# SCHEMATICS.net
KiCad netlist of a schematic drawn in EAGLE
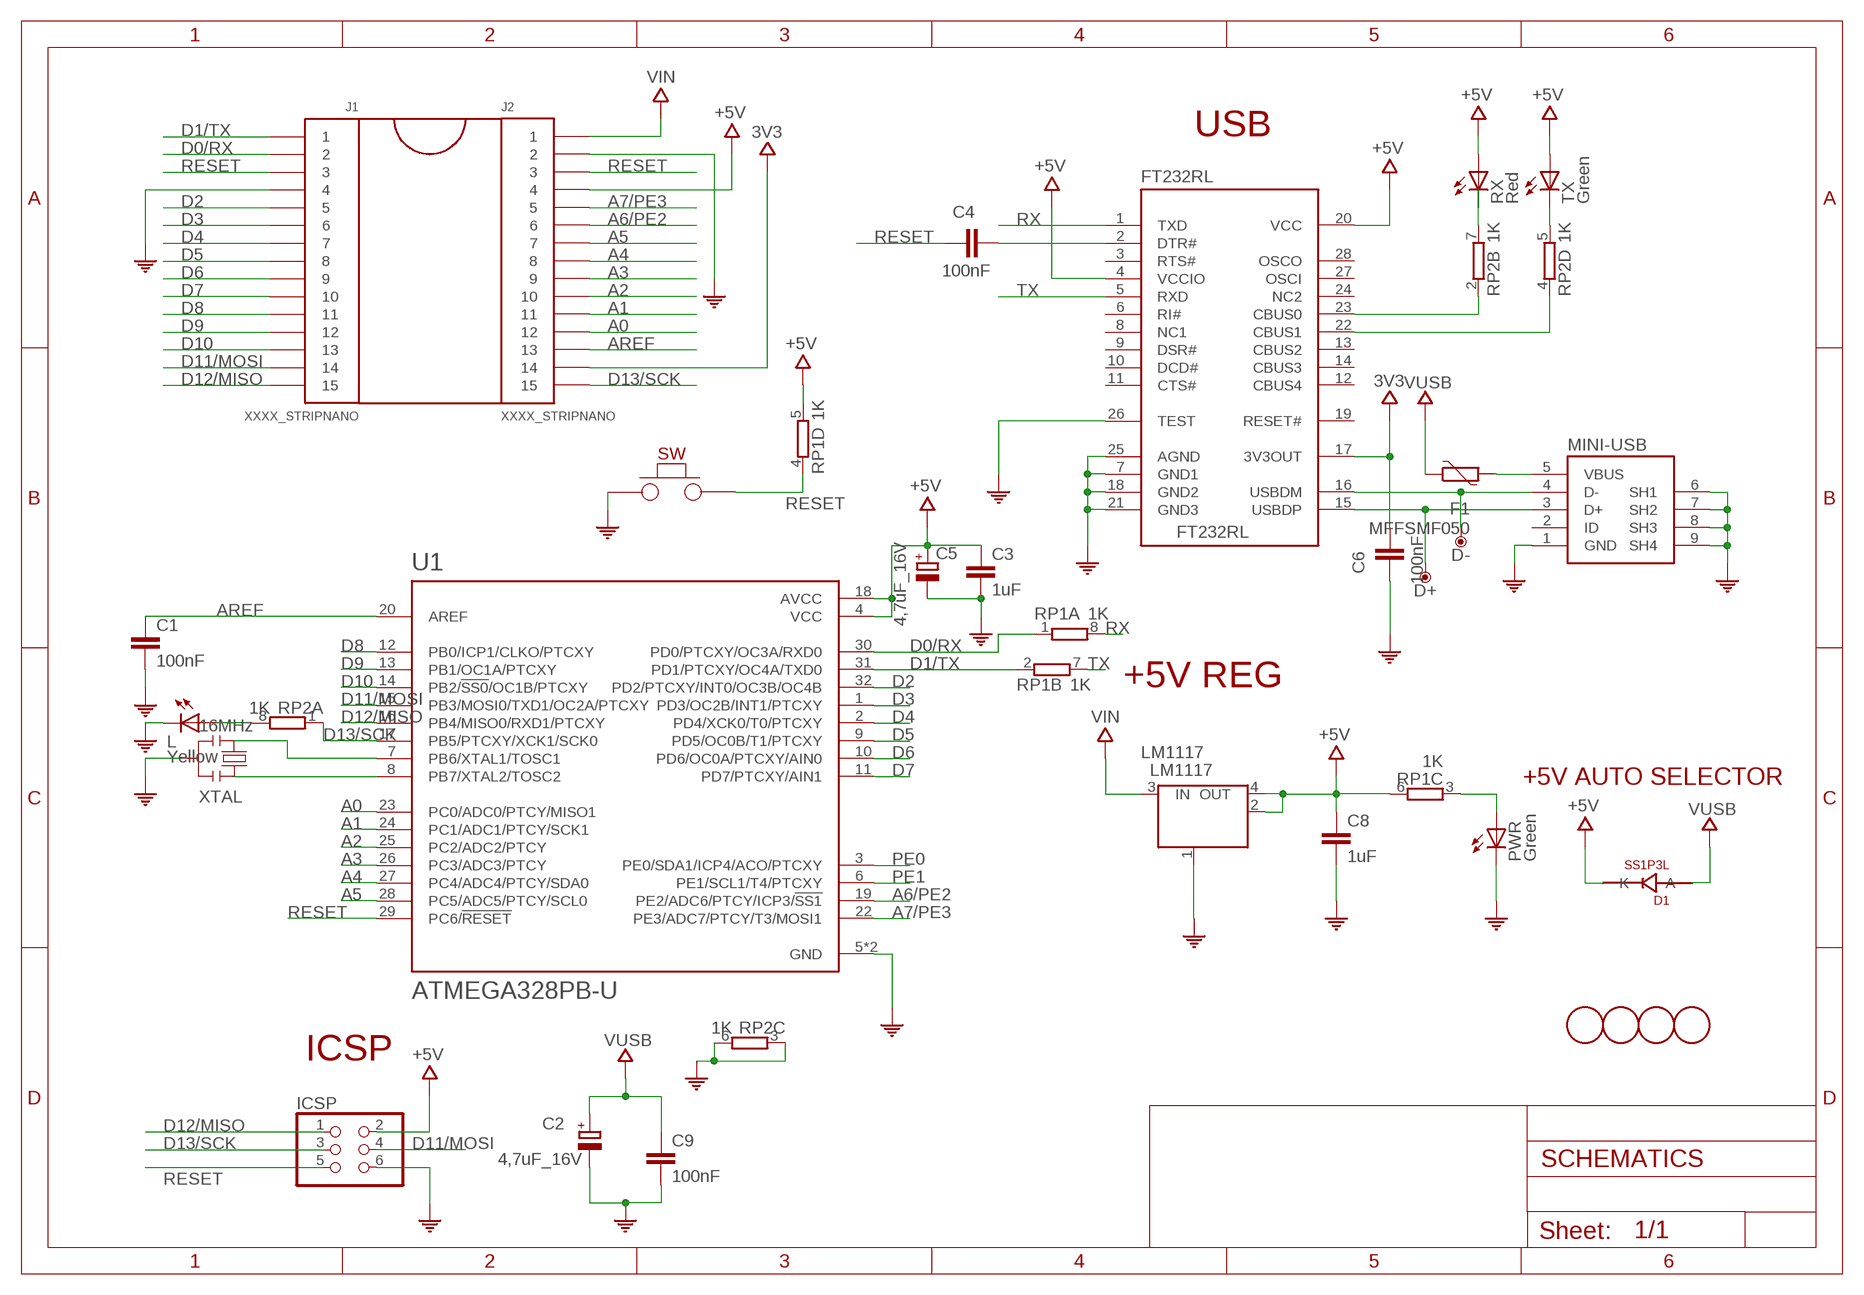
[diagram p0: schematic, sheet 1]

(export (version "E")
  (design (tool "Eeschema 10.0.6"))
  (components
    (comp (ref "C1")
      (value "100nF")
      (footprint "eagle-import:C0603-ROUND")
      (fields (field (name "PART_NUMBER") "cl10b104kbnc"))
      (libsource (lib "eagle-import") (part "0015_100NF_0603"))
    )
    (comp (ref "C2")
      (value "4,7uF_16V")
      (footprint "eagle-import:TAN-A")
      (fields (field (name "PART_NUMBER") "TAJA475MO16RNJ"))
      (libsource (lib "eagle-import") (part "0833_TAJA475MO16RNJ"))
    )
    (comp (ref "C3")
      (value "1uF")
      (footprint "eagle-import:C0603-ROUND")
      (fields (field (name "PART_NUMBER") "1uF_0603/GRM188R61E105KA12D"))
      (libsource (lib "eagle-import") (part "0006_1UF_0603/GRM188R61E105KA12D"))
    )
    (comp (ref "C4")
      (value "100nF")
      (footprint "eagle-import:C0603-ROUND")
      (fields (field (name "PART_NUMBER") "cl10b104kbnc"))
      (libsource (lib "eagle-import") (part "0015_100NF_0603"))
    )
    (comp (ref "C5")
      (value "4,7uF_16V")
      (footprint "eagle-import:TAN-A")
      (fields (field (name "PART_NUMBER") "TAJA475MO16RNJ"))
      (libsource (lib "eagle-import") (part "0833_TAJA475MO16RNJ"))
    )
    (comp (ref "C6")
      (value "100nF")
      (footprint "eagle-import:C0603-ROUND")
      (fields (field (name "PART_NUMBER") "cl10b104kbnc"))
      (libsource (lib "eagle-import") (part "0015_100NF_0603"))
    )
    (comp (ref "C8")
      (value "1uF")
      (footprint "eagle-import:C0603-ROUND")
      (fields (field (name "PART_NUMBER") "1uF_0603/GRM188R61E105KA12D"))
      (libsource (lib "eagle-import") (part "0006_1UF_0603/GRM188R61E105KA12D"))
    )
    (comp (ref "C9")
      (value "100nF")
      (footprint "eagle-import:C0603-ROUND")
      (fields (field (name "PART_NUMBER") "cl10b104kbnc"))
      (libsource (lib "eagle-import") (part "0015_100NF_0603"))
    )
    (comp (ref "D+")
      (value "DNP")
      (footprint "eagle-import:TP-1.00MM")
      (libsource (lib "eagle-import") (part "TPTP-1.00MM"))
    )
    (comp (ref "D-")
      (value "DNP")
      (footprint "eagle-import:TP-1.00MM")
      (libsource (lib "eagle-import") (part "TPTP-1.00MM"))
    )
    (comp (ref "D1")
      (value "SS1P3L")
      (footprint "eagle-import:DO220AAL")
      (fields (field (name "PART_NUMBER") "SS1P3L-M3/84A"))
      (libsource (lib "eagle-import") (part "0025_SS1P3L-M3/84A"))
    )
    (comp (ref "F1")
      (value "MFFSMF050")
      (footprint "eagle-import:0603-1608X90N")
      (fields (field (name "MANUFACTURER") "Bourns Inc "))
      (libsource (lib "eagle-import") (part "PTC"))
    )
    (comp (ref "FT232RL")
      (value "FT232RL")
      (footprint "eagle-import:SSOP28")
      (libsource (lib "eagle-import") (part "0226_FT232RL"))
    )
    (comp (ref "ICSP")
      (value "0114_PH254-203DF118A00V")
      (footprint "eagle-import:2X03")
      (fields (field (name "PART_NUMBER") "PH254-203DF118A00V"))
      (libsource (lib "eagle-import") (part "0114_PH254-203DF118A00V"))
    )
    (comp (ref "J1")
      (value "XXXX_STRIPNANO")
      (footprint "eagle-import:HEAD15-NOSS")
      (libsource (lib "eagle-import") (part "XXXX_STRIPNANO"))
    )
    (comp (ref "J2")
      (value "XXXX_STRIPNANO")
      (footprint "eagle-import:HEAD15-NOSS")
      (libsource (lib "eagle-import") (part "XXXX_STRIPNANO"))
    )
    (comp (ref "L")
      (value "Yellow")
      (footprint "eagle-import:CHIPLED_0805")
      (fields (field (name "PART_NUMBER") "KPT-2012YC"))
      (libsource (lib "eagle-import") (part "0044_KPT-2012YC"))
    )
    (comp (ref "LM1117")
      (value "LM1117")
      (footprint "eagle-import:LINEAR_SOT223")
      (fields (field (name "PART_NUMBER") "LM1117IMPX-5.0"))
      (libsource (lib "eagle-import") (part "0022_LM1117IMPX-5.0"))
    )
    (comp (ref "MINI-USB")
      (value "0219_14850")
      (footprint "eagle-import:USB-MINI-B_2")
      (fields (field (name "PART_NUMBER") "14850"))
      (libsource (lib "eagle-import") (part "0219_14850"))
    )
    (comp (ref "P0INT_2")
      (value "DNP")
      (footprint "eagle-import:FD-1-1.5")
      (libsource (lib "eagle-import") (part "FIDUCIAL-1.5MM"))
    )
    (comp (ref "POINT_1")
      (value "DNP")
      (footprint "eagle-import:FD-1-1.5")
      (libsource (lib "eagle-import") (part "FIDUCIAL-1.5MM"))
    )
    (comp (ref "POINT_A")
      (value "DNP")
      (footprint "eagle-import:FD-1-1.5")
      (libsource (lib "eagle-import") (part "FIDUCIAL-1.5MM"))
    )
    (comp (ref "POINT_B")
      (value "DNP")
      (footprint "eagle-import:FD-1-1.5")
      (libsource (lib "eagle-import") (part "FIDUCIAL-1.5MM"))
    )
    (comp (ref "PWR")
      (value "Green")
      (footprint "eagle-import:CHIPLED_0805")
      (fields (field (name "PART_NUMBER") "KPT-2012SGC"))
      (libsource (lib "eagle-import") (part "0043_KPT-2012SGC"))
    )
    (comp (ref "RP1")
      (value "1K")
      (footprint "eagle-import:CAY16")
      (fields (field (name "PART_NUMBER") "064R_1K_/_CAY16-102J4LF"))
      (libsource (lib "eagle-import") (part "0005_064R_1K_/_CAY16-102J4LF"))
    )
    (comp (ref "RP2")
      (value "1K")
      (footprint "eagle-import:CAY16")
      (fields (field (name "PART_NUMBER") "064R_1K_/_CAY16-102J4LF"))
      (libsource (lib "eagle-import") (part "0005_064R_1K_/_CAY16-102J4LF"))
    )
    (comp (ref "RX")
      (value "Red")
      (footprint "eagle-import:CHIPLED_0805")
      (fields (field (name "PART_NUMBER") "KTP-2012SURCK"))
      (libsource (lib "eagle-import") (part "0181_KTP-2012SURCK"))
    )
    (comp (ref "TX")
      (value "Green")
      (footprint "eagle-import:CHIPLED_0805")
      (fields (field (name "PART_NUMBER") "KPT-2012SGC"))
      (libsource (lib "eagle-import") (part "0043_KPT-2012SGC"))
    )
    (comp (ref "U$4")
      (value "3*6*4.2H260g")
      (footprint "eagle-import:3_6_4.3_PUSH_SWITCH")
      (libsource (lib "eagle-import") (part "364.3_PUSH_SWITCH"))
    )
    (comp (ref "U1")
      (value "ATMEGA328PB-U")
      (footprint "eagle-import:QFP80P900X900X120-32N")
      (fields (field (name "MF") "Microchip Technology"))
      (libsource (lib "eagle-import") (part "ATMEGA328PB-AN"))
    )
    (comp (ref "XTAL")
      (value "16MHz")
      (footprint "eagle-import:RESONATOR")
      (fields (field (name "PART_NUMBER") "CSTCE16M0V53-R0"))
      (libsource (lib "eagle-import") (part "0011_CSTCE16M0V53-R0"))
    )
  )
  (nets
    (net (code "1") (name "+5V") (class "Default")
      (node (ref "C3") (pin "1") (pinfunction "1_1") (pintype "passive"))
      (node (ref "C5") (pin "1") (pinfunction "+_1") (pintype "passive"))
      (node (ref "C8") (pin "1") (pinfunction "1_1") (pintype "passive"))
      (node (ref "D1") (pin "P$1") (pinfunction "K_P$1") (pintype "bidirectional"))
      (node (ref "FT232RL") (pin "20") (pinfunction "VCC_20") (pintype "power_in"))
      (node (ref "FT232RL") (pin "4") (pinfunction "VCCIO_4") (pintype "power_in"))
      (node (ref "ICSP") (pin "2") (pinfunction "2_2") (pintype "passive"))
      (node (ref "J2") (pin "4") (pinfunction "4_4") (pintype "passive"))
      (node (ref "LM1117") (pin "2") (pinfunction "OUT_2") (pintype "passive"))
      (node (ref "LM1117") (pin "4") (pinfunction "OUT_4") (pintype "passive"))
      (node (ref "RP1") (pin "5") (pinfunction "2_5") (pintype "passive"))
      (node (ref "RP1") (pin "6") (pinfunction "2_6") (pintype "passive"))
      (node (ref "RX") (pin "A") (pinfunction "A_A") (pintype "passive"))
      (node (ref "TX") (pin "A") (pinfunction "A_A") (pintype "passive"))
      (node (ref "U1") (pin "18") (pinfunction "AVCC_18") (pintype "power_in"))
      (node (ref "U1") (pin "4") (pinfunction "VCC_4") (pintype "power_in"))
    )
    (net (code "2") (name "/A0") (class "Default")
      (node (ref "J2") (pin "12") (pinfunction "12_12") (pintype "passive"))
      (node (ref "U1") (pin "23") (pinfunction "PC0/ADC0/PTCY/MISO1_23") (pintype "bidirectional"))
    )
    (net (code "3") (name "/A1") (class "Default")
      (node (ref "J2") (pin "11") (pinfunction "11_11") (pintype "passive"))
      (node (ref "U1") (pin "24") (pinfunction "PC1/ADC1/PTCY/SCK1_24") (pintype "bidirectional"))
    )
    (net (code "4") (name "/A2") (class "Default")
      (node (ref "J2") (pin "10") (pinfunction "10_10") (pintype "passive"))
      (node (ref "U1") (pin "25") (pinfunction "PC2/ADC2/PTCY_25") (pintype "bidirectional"))
    )
    (net (code "5") (name "/A3") (class "Default")
      (node (ref "J2") (pin "9") (pinfunction "9_9") (pintype "passive"))
      (node (ref "U1") (pin "26") (pinfunction "PC3/ADC3/PTCY_26") (pintype "bidirectional"))
    )
    (net (code "6") (name "/A4") (class "Default")
      (node (ref "J2") (pin "8") (pinfunction "8_8") (pintype "passive"))
      (node (ref "U1") (pin "27") (pinfunction "PC4/ADC4/PTCY/SDA0_27") (pintype "bidirectional"))
    )
    (net (code "7") (name "/A5") (class "Default")
      (node (ref "J2") (pin "7") (pinfunction "7_7") (pintype "passive"))
      (node (ref "U1") (pin "28") (pinfunction "PC5/ADC5/PTCY/SCL0_28") (pintype "bidirectional"))
    )
    (net (code "8") (name "/A6{slash}PE2") (class "Default")
      (node (ref "J2") (pin "6") (pinfunction "6_6") (pintype "passive"))
      (node (ref "U1") (pin "19") (pinfunction "PE2/ADC6/PTCY/ICP3/~{SS1}_19") (pintype "bidirectional"))
    )
    (net (code "9") (name "/A7{slash}PE3") (class "Default")
      (node (ref "J2") (pin "5") (pinfunction "5_5") (pintype "passive"))
      (node (ref "U1") (pin "22") (pinfunction "PE3/ADC7/PTCY/T3/MOSI1_22") (pintype "bidirectional"))
    )
    (net (code "10") (name "/AREF") (class "Default")
      (node (ref "C1") (pin "1") (pinfunction "1_1") (pintype "passive"))
      (node (ref "J2") (pin "13") (pinfunction "13_13") (pintype "passive"))
      (node (ref "U1") (pin "20") (pinfunction "AREF_20") (pintype "input"))
    )
    (net (code "11") (name "/D0{slash}RX") (class "Default")
      (node (ref "J1") (pin "2") (pinfunction "2_2") (pintype "passive"))
      (node (ref "RP1") (pin "1") (pinfunction "1_1") (pintype "passive"))
      (node (ref "U1") (pin "30") (pinfunction "PD0/PTCXY/OC3A/RXD0_30") (pintype "bidirectional"))
    )
    (net (code "12") (name "/D1{slash}TX") (class "Default")
      (node (ref "J1") (pin "1") (pinfunction "1_1") (pintype "passive"))
      (node (ref "RP1") (pin "2") (pinfunction "1_2") (pintype "passive"))
      (node (ref "U1") (pin "31") (pinfunction "PD1/PTCXY/OC4A/TXD0_31") (pintype "bidirectional"))
    )
    (net (code "13") (name "/D2") (class "Default")
      (node (ref "J1") (pin "5") (pinfunction "5_5") (pintype "passive"))
      (node (ref "U1") (pin "32") (pinfunction "PD2/PTCXY/INT0/OC3B/OC4B_32") (pintype "bidirectional"))
    )
    (net (code "14") (name "/D3") (class "Default")
      (node (ref "J1") (pin "6") (pinfunction "6_6") (pintype "passive"))
      (node (ref "U1") (pin "1") (pinfunction "PD3/OC2B/INT1/PTCXY_1") (pintype "bidirectional"))
    )
    (net (code "15") (name "/D4") (class "Default")
      (node (ref "J1") (pin "7") (pinfunction "7_7") (pintype "passive"))
      (node (ref "U1") (pin "2") (pinfunction "PD4/XCK0/T0/PTCXY_2") (pintype "bidirectional"))
    )
    (net (code "16") (name "/D5") (class "Default")
      (node (ref "J1") (pin "8") (pinfunction "8_8") (pintype "passive"))
      (node (ref "U1") (pin "9") (pinfunction "PD5/OC0B/T1/PTCXY_9") (pintype "bidirectional"))
    )
    (net (code "17") (name "/D6") (class "Default")
      (node (ref "J1") (pin "9") (pinfunction "9_9") (pintype "passive"))
      (node (ref "U1") (pin "10") (pinfunction "PD6/OC0A/PTCXY/AIN0_10") (pintype "bidirectional"))
    )
    (net (code "18") (name "/D7") (class "Default")
      (node (ref "J1") (pin "10") (pinfunction "10_10") (pintype "passive"))
      (node (ref "U1") (pin "11") (pinfunction "PD7/PTCXY/AIN1_11") (pintype "bidirectional"))
    )
    (net (code "19") (name "/D8") (class "Default")
      (node (ref "J1") (pin "11") (pinfunction "11_11") (pintype "passive"))
      (node (ref "U1") (pin "12") (pinfunction "PB0/ICP1/CLKO/PTCXY_12") (pintype "bidirectional"))
    )
    (net (code "20") (name "/D9") (class "Default")
      (node (ref "J1") (pin "12") (pinfunction "12_12") (pintype "passive"))
      (node (ref "U1") (pin "13") (pinfunction "PB1/OC1A/PTCXY_13") (pintype "bidirectional"))
    )
    (net (code "21") (name "/D10") (class "Default")
      (node (ref "J1") (pin "13") (pinfunction "13_13") (pintype "passive"))
      (node (ref "U1") (pin "14") (pinfunction "PB2/~{SS0}/OC1B/PTCXY_14") (pintype "bidirectional"))
    )
    (net (code "22") (name "/D11{slash}MOSI") (class "Default")
      (node (ref "ICSP") (pin "4") (pinfunction "4_4") (pintype "passive"))
      (node (ref "J1") (pin "14") (pinfunction "14_14") (pintype "passive"))
      (node (ref "U1") (pin "15") (pinfunction "PB3/MOSI0/TXD1/OC2A/PTCXY_15") (pintype "bidirectional"))
    )
    (net (code "23") (name "/D12{slash}MISO") (class "Default")
      (node (ref "ICSP") (pin "1") (pinfunction "1_1") (pintype "passive"))
      (node (ref "J1") (pin "15") (pinfunction "15_15") (pintype "passive"))
      (node (ref "U1") (pin "16") (pinfunction "PB4/MISO0/RXD1/PTCXY_16") (pintype "bidirectional"))
    )
    (net (code "24") (name "/D13{slash}SCK") (class "Default")
      (node (ref "ICSP") (pin "3") (pinfunction "3_3") (pintype "passive"))
      (node (ref "J2") (pin "15") (pinfunction "15_15") (pintype "passive"))
      (node (ref "RP2") (pin "1") (pinfunction "1_1") (pintype "passive"))
      (node (ref "U1") (pin "17") (pinfunction "PB5/PTCXY/XCK1/SCK0_17") (pintype "bidirectional"))
    )
    (net (code "25") (name "/PE0") (class "Default")
      (node (ref "U1") (pin "3") (pinfunction "PE0/SDA1/ICP4/ACO/PTCXY_3") (pintype "bidirectional"))
    )
    (net (code "26") (name "/PE1") (class "Default")
      (node (ref "U1") (pin "6") (pinfunction "PE1/SCL1/T4/PTCXY_6") (pintype "bidirectional"))
    )
    (net (code "27") (name "/RESET") (class "Default")
      (node (ref "C4") (pin "1") (pinfunction "1_1") (pintype "passive"))
      (node (ref "ICSP") (pin "5") (pinfunction "5_5") (pintype "passive"))
      (node (ref "J1") (pin "3") (pinfunction "3_3") (pintype "passive"))
      (node (ref "J2") (pin "3") (pinfunction "3_3") (pintype "passive"))
      (node (ref "RP1") (pin "4") (pinfunction "1_4") (pintype "passive"))
      (node (ref "U$4") (pin "P$2") (pinfunction "P$2_P$2") (pintype "bidirectional"))
      (node (ref "U1") (pin "29") (pinfunction "PC6/~{RESET}_29") (pintype "bidirectional"))
    )
    (net (code "28") (name "/RX") (class "Default")
      (node (ref "FT232RL") (pin "1") (pinfunction "TXD_1") (pintype "output"))
      (node (ref "RP1") (pin "8") (pinfunction "2_8") (pintype "passive"))
    )
    (net (code "29") (name "/TX") (class "Default")
      (node (ref "FT232RL") (pin "5") (pinfunction "RXD_5") (pintype "input"))
      (node (ref "RP1") (pin "7") (pinfunction "2_7") (pintype "passive"))
    )
    (net (code "30") (name "3V3") (class "Default")
      (node (ref "C6") (pin "2") (pinfunction "2_2") (pintype "passive"))
      (node (ref "FT232RL") (pin "17") (pinfunction "3V3OUT_17") (pintype "power_in"))
      (node (ref "J2") (pin "14") (pinfunction "14_14") (pintype "passive"))
    )
    (net (code "31") (name "COM") (class "Default")
      (node (ref "C1") (pin "2") (pinfunction "2_2") (pintype "passive"))
      (node (ref "C2") (pin "2") (pinfunction "-_2") (pintype "passive"))
      (node (ref "C3") (pin "2") (pinfunction "2_2") (pintype "passive"))
      (node (ref "C5") (pin "2") (pinfunction "-_2") (pintype "passive"))
      (node (ref "C6") (pin "1") (pinfunction "1_1") (pintype "passive"))
      (node (ref "C8") (pin "2") (pinfunction "2_2") (pintype "passive"))
      (node (ref "C9") (pin "2") (pinfunction "2_2") (pintype "passive"))
      (node (ref "FT232RL") (pin "18") (pinfunction "GND2_18") (pintype "power_in"))
      (node (ref "FT232RL") (pin "21") (pinfunction "GND3_21") (pintype "power_in"))
      (node (ref "FT232RL") (pin "25") (pinfunction "AGND_25") (pintype "power_in"))
      (node (ref "FT232RL") (pin "26") (pinfunction "TEST_26") (pintype "bidirectional"))
      (node (ref "FT232RL") (pin "7") (pinfunction "GND1_7") (pintype "power_in"))
      (node (ref "ICSP") (pin "6") (pinfunction "6_6") (pintype "passive"))
      (node (ref "J1") (pin "4") (pinfunction "4_4") (pintype "passive"))
      (node (ref "J2") (pin "2") (pinfunction "2_2") (pintype "passive"))
      (node (ref "L") (pin "C") (pinfunction "C_C") (pintype "passive"))
      (node (ref "LM1117") (pin "1") (pinfunction "GND/ADJ_1") (pintype "input"))
      (node (ref "MINI-USB") (pin "1") (pinfunction "GND_1") (pintype "passive"))
      (node (ref "MINI-USB") (pin "6") (pinfunction "SH1_6") (pintype "passive"))
      (node (ref "MINI-USB") (pin "7") (pinfunction "SH2_7") (pintype "passive"))
      (node (ref "MINI-USB") (pin "8") (pinfunction "SH3_8") (pintype "passive"))
      (node (ref "MINI-USB") (pin "9") (pinfunction "SH4_9") (pintype "passive"))
      (node (ref "PWR") (pin "C") (pinfunction "C_C") (pintype "passive"))
      (node (ref "RP2") (pin "3") (pinfunction "1_3") (pintype "passive"))
      (node (ref "RP2") (pin "6") (pinfunction "2_6") (pintype "passive"))
      (node (ref "U$4") (pin "P$1") (pinfunction "P$1_P$1") (pintype "bidirectional"))
      (node (ref "U1") (pin "21") (pinfunction "GND_21") (pintype "power_in"))
      (node (ref "U1") (pin "5") (pinfunction "GND_5") (pintype "power_in"))
      (node (ref "XTAL") (pin "2") (pinfunction "2_2") (pintype "passive"))
    )
    (net (code "32") (name "Net-(D+-P$1)") (class "Default")
      (node (ref "D+") (pin "X") (pinfunction "P$1_X") (pintype "passive"))
      (node (ref "FT232RL") (pin "15") (pinfunction "USBDP_15") (pintype "bidirectional"))
      (node (ref "MINI-USB") (pin "3") (pinfunction "D+_3") (pintype "bidirectional"))
    )
    (net (code "33") (name "Net-(D--P$1)") (class "Default")
      (node (ref "D-") (pin "X") (pinfunction "P$1_X") (pintype "passive"))
      (node (ref "FT232RL") (pin "16") (pinfunction "USBDM_16") (pintype "bidirectional"))
      (node (ref "MINI-USB") (pin "4") (pinfunction "D-_4") (pintype "bidirectional"))
    )
    (net (code "34") (name "Net-(FT232RL-CBUS0)") (class "Default")
      (node (ref "FT232RL") (pin "23") (pinfunction "CBUS0_23") (pintype "bidirectional"))
      (node (ref "RP2") (pin "2") (pinfunction "1_2") (pintype "passive"))
    )
    (net (code "35") (name "Net-(FT232RL-CBUS1)") (class "Default")
      (node (ref "FT232RL") (pin "22") (pinfunction "CBUS1_22") (pintype "bidirectional"))
      (node (ref "RP2") (pin "4") (pinfunction "1_4") (pintype "passive"))
    )
    (net (code "36") (name "Net-(FT232RL-DTR#)") (class "Default")
      (node (ref "C4") (pin "2") (pinfunction "2_2") (pintype "passive"))
      (node (ref "FT232RL") (pin "2") (pinfunction "DTR#_2") (pintype "output"))
    )
    (net (code "37") (name "Net-(MINI-USB-VBUS)") (class "Default")
      (node (ref "F1") (pin "2") (pinfunction "2_2") (pintype "passive"))
      (node (ref "MINI-USB") (pin "5") (pinfunction "VBUS_5") (pintype "power_in"))
    )
    (net (code "38") (name "Net-(RP1C-1)") (class "Default")
      (node (ref "PWR") (pin "A") (pinfunction "A_A") (pintype "passive"))
      (node (ref "RP1") (pin "3") (pinfunction "1_3") (pintype "passive"))
    )
    (net (code "39") (name "Net-(RP2A-2)") (class "Default")
      (node (ref "L") (pin "A") (pinfunction "A_A") (pintype "passive"))
      (node (ref "RP2") (pin "8") (pinfunction "2_8") (pintype "passive"))
    )
    (net (code "40") (name "Net-(RP2B-2)") (class "Default")
      (node (ref "RP2") (pin "7") (pinfunction "2_7") (pintype "passive"))
      (node (ref "RX") (pin "C") (pinfunction "C_C") (pintype "passive"))
    )
    (net (code "41") (name "Net-(RP2D-2)") (class "Default")
      (node (ref "RP2") (pin "5") (pinfunction "2_5") (pintype "passive"))
      (node (ref "TX") (pin "C") (pinfunction "C_C") (pintype "passive"))
    )
    (net (code "42") (name "Net-(U1-PB6{slash}XTAL1{slash}TOSC1)") (class "Default")
      (node (ref "U1") (pin "7") (pinfunction "PB6/XTAL1/TOSC1_7") (pintype "bidirectional"))
      (node (ref "XTAL") (pin "3") (pinfunction "3_3") (pintype "passive"))
    )
    (net (code "43") (name "Net-(U1-PB7{slash}XTAL2{slash}TOSC2)") (class "Default")
      (node (ref "U1") (pin "8") (pinfunction "PB7/XTAL2/TOSC2_8") (pintype "bidirectional"))
      (node (ref "XTAL") (pin "1") (pinfunction "1_1") (pintype "passive"))
    )
    (net (code "44") (name "VIN") (class "Default")
      (node (ref "J2") (pin "1") (pinfunction "1_1") (pintype "passive"))
      (node (ref "LM1117") (pin "3") (pinfunction "IN_3") (pintype "input"))
    )
    (net (code "45") (name "VUSB") (class "Default")
      (node (ref "C2") (pin "1") (pinfunction "+_1") (pintype "passive"))
      (node (ref "C9") (pin "1") (pinfunction "1_1") (pintype "passive"))
      (node (ref "D1") (pin "P$2") (pinfunction "A_P$2") (pintype "bidirectional"))
      (node (ref "F1") (pin "1") (pinfunction "1_1") (pintype "passive"))
    )
    (net (code "46") (name "unconnected-(FT232RL-CBUS2-Pad13)") (class "Default")
      (node (ref "FT232RL") (pin "13") (pinfunction "CBUS2_13") (pintype "bidirectional"))
    )
    (net (code "47") (name "unconnected-(FT232RL-CBUS3-Pad14)") (class "Default")
      (node (ref "FT232RL") (pin "14") (pinfunction "CBUS3_14") (pintype "bidirectional"))
    )
    (net (code "48") (name "unconnected-(FT232RL-CBUS4-Pad12)") (class "Default")
      (node (ref "FT232RL") (pin "12") (pinfunction "CBUS4_12") (pintype "bidirectional"))
    )
    (net (code "49") (name "unconnected-(FT232RL-CTS#-Pad11)") (class "Default")
      (node (ref "FT232RL") (pin "11") (pinfunction "CTS#_11") (pintype "bidirectional"))
    )
    (net (code "50") (name "unconnected-(FT232RL-DCD#-Pad10)") (class "Default")
      (node (ref "FT232RL") (pin "10") (pinfunction "DCD#_10") (pintype "bidirectional"))
    )
    (net (code "51") (name "unconnected-(FT232RL-DSR#-Pad9)") (class "Default")
      (node (ref "FT232RL") (pin "9") (pinfunction "DSR#_9") (pintype "bidirectional"))
    )
    (net (code "52") (name "unconnected-(FT232RL-NC1-Pad8)") (class "Default")
      (node (ref "FT232RL") (pin "8") (pinfunction "NC1_8") (pintype "bidirectional"))
    )
    (net (code "53") (name "unconnected-(FT232RL-NC2-Pad24)") (class "Default")
      (node (ref "FT232RL") (pin "24") (pinfunction "NC2_24") (pintype "no_connect"))
    )
    (net (code "54") (name "unconnected-(FT232RL-OSCI-Pad27)") (class "Default")
      (node (ref "FT232RL") (pin "27") (pinfunction "OSCI_27") (pintype "bidirectional"))
    )
    (net (code "55") (name "unconnected-(FT232RL-OSCO-Pad28)") (class "Default")
      (node (ref "FT232RL") (pin "28") (pinfunction "OSCO_28") (pintype "output"))
    )
    (net (code "56") (name "unconnected-(FT232RL-RESET#-Pad19)") (class "Default")
      (node (ref "FT232RL") (pin "19") (pinfunction "RESET#_19") (pintype "bidirectional"))
    )
    (net (code "57") (name "unconnected-(FT232RL-RI#-Pad6)") (class "Default")
      (node (ref "FT232RL") (pin "6") (pinfunction "RI#_6") (pintype "bidirectional"))
    )
    (net (code "58") (name "unconnected-(FT232RL-RTS#-Pad3)") (class "Default")
      (node (ref "FT232RL") (pin "3") (pinfunction "RTS#_3") (pintype "output"))
    )
    (net (code "59") (name "unconnected-(MINI-USB-ID-Pad2)") (class "Default")
      (node (ref "MINI-USB") (pin "2") (pinfunction "ID_2") (pintype "bidirectional"))
    )
  )
)
